# breadboard-small-with-header.net
KiCad netlist of a schematic drawn in EAGLE
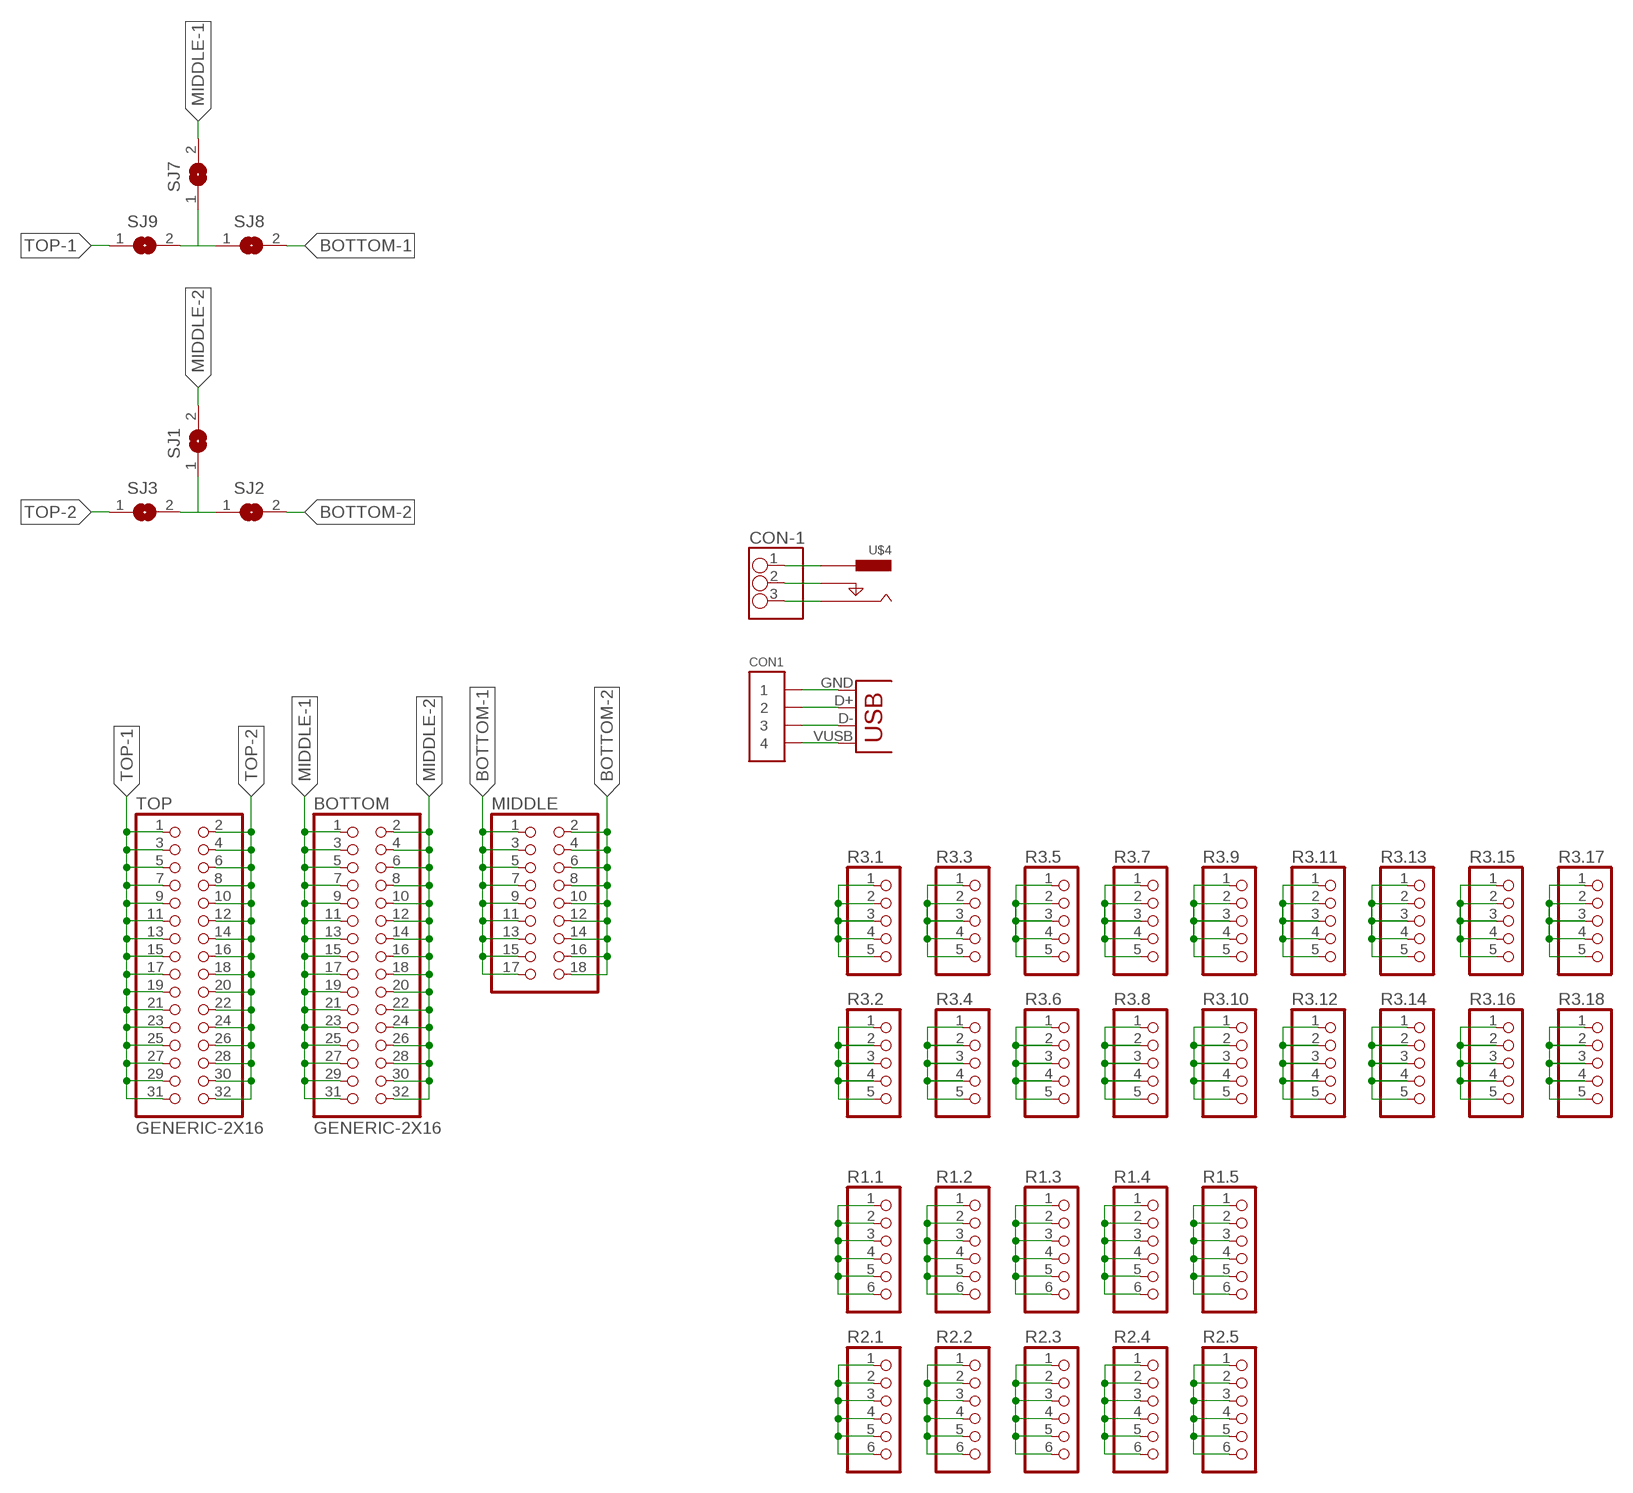
[diagram p0: schematic, sheet 1]

(export (version "E")
  (design (tool "Eeschema 10.0.6"))
  (components
    (comp (ref "BOTTOM")
      (value "GENERIC-2X16")
      (footprint "eagle-import:PINHEADER-100MIL-2X16-NOSILK")
      (libsource (lib "eagle-import") (part "GENERIC-2X16"))
    )
    (comp (ref "CON-1")
      (value "GENERIC-1X3")
      (footprint "eagle-import:PINHEADER-100MIL-1X3-NOSILK")
      (libsource (lib "eagle-import") (part "GENERIC-1X3"))
    )
    (comp (ref "CON1")
      (value "GENERIC-1X4STRAIGHT")
      (footprint "eagle-import:PINHEADER-100MIL-1X4-NOSILK")
      (libsource (lib "eagle-import") (part "GENERIC-1X4STRAIGHT"))
    )
    (comp (ref "MIDDLE")
      (value "GENERIC-2X9")
      (footprint "eagle-import:PINHEADER-100MIL-2X9-NOSILK")
      (libsource (lib "eagle-import") (part "GENERIC-2X9"))
    )
    (comp (ref "R1.1")
      (value "GENERIC-1X6")
      (footprint "eagle-import:PINHEADER-100MIL-1X6-NOSILK")
      (libsource (lib "eagle-import") (part "GENERIC-1X6"))
    )
    (comp (ref "R1.2")
      (value "GENERIC-1X6")
      (footprint "eagle-import:PINHEADER-100MIL-1X6-NOSILK")
      (libsource (lib "eagle-import") (part "GENERIC-1X6"))
    )
    (comp (ref "R1.3")
      (value "GENERIC-1X6")
      (footprint "eagle-import:PINHEADER-100MIL-1X6-NOSILK")
      (libsource (lib "eagle-import") (part "GENERIC-1X6"))
    )
    (comp (ref "R1.4")
      (value "GENERIC-1X6")
      (footprint "eagle-import:PINHEADER-100MIL-1X6-NOSILK")
      (libsource (lib "eagle-import") (part "GENERIC-1X6"))
    )
    (comp (ref "R1.5")
      (value "GENERIC-1X6")
      (footprint "eagle-import:PINHEADER-100MIL-1X6-NOSILK")
      (libsource (lib "eagle-import") (part "GENERIC-1X6"))
    )
    (comp (ref "R2.1")
      (value "GENERIC-1X6")
      (footprint "eagle-import:PINHEADER-100MIL-1X6-NOSILK")
      (libsource (lib "eagle-import") (part "GENERIC-1X6"))
    )
    (comp (ref "R2.2")
      (value "GENERIC-1X6")
      (footprint "eagle-import:PINHEADER-100MIL-1X6-NOSILK")
      (libsource (lib "eagle-import") (part "GENERIC-1X6"))
    )
    (comp (ref "R2.3")
      (value "GENERIC-1X6")
      (footprint "eagle-import:PINHEADER-100MIL-1X6-NOSILK")
      (libsource (lib "eagle-import") (part "GENERIC-1X6"))
    )
    (comp (ref "R2.4")
      (value "GENERIC-1X6")
      (footprint "eagle-import:PINHEADER-100MIL-1X6-NOSILK")
      (libsource (lib "eagle-import") (part "GENERIC-1X6"))
    )
    (comp (ref "R2.5")
      (value "GENERIC-1X6")
      (footprint "eagle-import:PINHEADER-100MIL-1X6-NOSILK")
      (libsource (lib "eagle-import") (part "GENERIC-1X6"))
    )
    (comp (ref "R3.1")
      (value "GENERIC-1X5")
      (footprint "eagle-import:PINHEADER-100MIL-1X5-NOSILK")
      (libsource (lib "eagle-import") (part "GENERIC-1X5"))
    )
    (comp (ref "R3.2")
      (value "GENERIC-1X5")
      (footprint "eagle-import:PINHEADER-100MIL-1X5-NOSILK")
      (libsource (lib "eagle-import") (part "GENERIC-1X5"))
    )
    (comp (ref "R3.3")
      (value "GENERIC-1X5")
      (footprint "eagle-import:PINHEADER-100MIL-1X5-NOSILK")
      (libsource (lib "eagle-import") (part "GENERIC-1X5"))
    )
    (comp (ref "R3.4")
      (value "GENERIC-1X5")
      (footprint "eagle-import:PINHEADER-100MIL-1X5-NOSILK")
      (libsource (lib "eagle-import") (part "GENERIC-1X5"))
    )
    (comp (ref "R3.5")
      (value "GENERIC-1X5")
      (footprint "eagle-import:PINHEADER-100MIL-1X5-NOSILK")
      (libsource (lib "eagle-import") (part "GENERIC-1X5"))
    )
    (comp (ref "R3.6")
      (value "GENERIC-1X5")
      (footprint "eagle-import:PINHEADER-100MIL-1X5-NOSILK")
      (libsource (lib "eagle-import") (part "GENERIC-1X5"))
    )
    (comp (ref "R3.7")
      (value "GENERIC-1X5")
      (footprint "eagle-import:PINHEADER-100MIL-1X5-NOSILK")
      (libsource (lib "eagle-import") (part "GENERIC-1X5"))
    )
    (comp (ref "R3.8")
      (value "GENERIC-1X5")
      (footprint "eagle-import:PINHEADER-100MIL-1X5-NOSILK")
      (libsource (lib "eagle-import") (part "GENERIC-1X5"))
    )
    (comp (ref "R3.9")
      (value "GENERIC-1X5")
      (footprint "eagle-import:PINHEADER-100MIL-1X5-NOSILK")
      (libsource (lib "eagle-import") (part "GENERIC-1X5"))
    )
    (comp (ref "R3.10")
      (value "GENERIC-1X5")
      (footprint "eagle-import:PINHEADER-100MIL-1X5-NOSILK")
      (libsource (lib "eagle-import") (part "GENERIC-1X5"))
    )
    (comp (ref "R3.11")
      (value "GENERIC-1X5")
      (footprint "eagle-import:PINHEADER-100MIL-1X5-NOSILK")
      (libsource (lib "eagle-import") (part "GENERIC-1X5"))
    )
    (comp (ref "R3.12")
      (value "GENERIC-1X5")
      (footprint "eagle-import:PINHEADER-100MIL-1X5-NOSILK")
      (libsource (lib "eagle-import") (part "GENERIC-1X5"))
    )
    (comp (ref "R3.13")
      (value "GENERIC-1X5")
      (footprint "eagle-import:PINHEADER-100MIL-1X5-NOSILK")
      (libsource (lib "eagle-import") (part "GENERIC-1X5"))
    )
    (comp (ref "R3.14")
      (value "GENERIC-1X5")
      (footprint "eagle-import:PINHEADER-100MIL-1X5-NOSILK")
      (libsource (lib "eagle-import") (part "GENERIC-1X5"))
    )
    (comp (ref "R3.15")
      (value "GENERIC-1X5")
      (footprint "eagle-import:PINHEADER-100MIL-1X5-NOSILK")
      (libsource (lib "eagle-import") (part "GENERIC-1X5"))
    )
    (comp (ref "R3.16")
      (value "GENERIC-1X5")
      (footprint "eagle-import:PINHEADER-100MIL-1X5-NOSILK")
      (libsource (lib "eagle-import") (part "GENERIC-1X5"))
    )
    (comp (ref "R3.17")
      (value "GENERIC-1X5")
      (footprint "eagle-import:PINHEADER-100MIL-1X5-NOSILK")
      (libsource (lib "eagle-import") (part "GENERIC-1X5"))
    )
    (comp (ref "R3.18")
      (value "GENERIC-1X5")
      (footprint "eagle-import:PINHEADER-100MIL-1X5-NOSILK")
      (libsource (lib "eagle-import") (part "GENERIC-1X5"))
    )
    (comp (ref "SJ1") (value "SJ") (footprint "eagle-import:SJ") (libsource (lib "eagle-import") (part "SJ")))
    (comp (ref "SJ2") (value "SJ") (footprint "eagle-import:SJ") (libsource (lib "eagle-import") (part "SJ")))
    (comp (ref "SJ3") (value "SJ") (footprint "eagle-import:SJ") (libsource (lib "eagle-import") (part "SJ")))
    (comp (ref "SJ7") (value "SJ") (footprint "eagle-import:SJ") (libsource (lib "eagle-import") (part "SJ")))
    (comp (ref "SJ8") (value "SJ") (footprint "eagle-import:SJ") (libsource (lib "eagle-import") (part "SJ")))
    (comp (ref "SJ9") (value "SJ") (footprint "eagle-import:SJ") (libsource (lib "eagle-import") (part "SJ")))
    (comp (ref "TOP")
      (value "GENERIC-2X16")
      (footprint "eagle-import:PINHEADER-100MIL-2X16-NOSILK")
      (libsource (lib "eagle-import") (part "GENERIC-2X16"))
    )
    (comp (ref "U$3")
      (value "USBMINI")
      (footprint "eagle-import:CONN_USB_MINI-B")
      (libsource (lib "eagle-import") (part "USBMINI"))
    )
    (comp (ref "U$4")
      (value "POWER-BARREL_JACKEBAY")
      (footprint "eagle-import:POWER-BARREL-2MM1-EBAY")
      (libsource (lib "eagle-import") (part "POWER-BARREL_JACKEBAY"))
    )
  )
  (nets
    (net (code "1") (name "BOTTOM-1") (class "Default")
      (node (ref "MIDDLE") (pin "1") (pinfunction "1_1") (pintype "passive"))
      (node (ref "MIDDLE") (pin "11") (pinfunction "11_11") (pintype "passive"))
      (node (ref "MIDDLE") (pin "13") (pinfunction "13_13") (pintype "passive"))
      (node (ref "MIDDLE") (pin "15") (pinfunction "15_15") (pintype "passive"))
      (node (ref "MIDDLE") (pin "17") (pinfunction "17_17") (pintype "passive"))
      (node (ref "MIDDLE") (pin "3") (pinfunction "3_3") (pintype "passive"))
      (node (ref "MIDDLE") (pin "5") (pinfunction "5_5") (pintype "passive"))
      (node (ref "MIDDLE") (pin "7") (pinfunction "7_7") (pintype "passive"))
      (node (ref "MIDDLE") (pin "9") (pinfunction "9_9") (pintype "passive"))
      (node (ref "SJ8") (pin "2") (pinfunction "2_2") (pintype "passive"))
    )
    (net (code "2") (name "BOTTOM-2") (class "Default")
      (node (ref "MIDDLE") (pin "10") (pinfunction "10_10") (pintype "passive"))
      (node (ref "MIDDLE") (pin "12") (pinfunction "12_12") (pintype "passive"))
      (node (ref "MIDDLE") (pin "14") (pinfunction "14_14") (pintype "passive"))
      (node (ref "MIDDLE") (pin "16") (pinfunction "16_16") (pintype "passive"))
      (node (ref "MIDDLE") (pin "18") (pinfunction "18_18") (pintype "passive"))
      (node (ref "MIDDLE") (pin "2") (pinfunction "2_2") (pintype "passive"))
      (node (ref "MIDDLE") (pin "4") (pinfunction "4_4") (pintype "passive"))
      (node (ref "MIDDLE") (pin "6") (pinfunction "6_6") (pintype "passive"))
      (node (ref "MIDDLE") (pin "8") (pinfunction "8_8") (pintype "passive"))
      (node (ref "SJ2") (pin "2") (pinfunction "2_2") (pintype "passive"))
    )
    (net (code "3") (name "MIDDLE-1") (class "Default")
      (node (ref "BOTTOM") (pin "1") (pinfunction "1_1") (pintype "passive"))
      (node (ref "BOTTOM") (pin "11") (pinfunction "11_11") (pintype "passive"))
      (node (ref "BOTTOM") (pin "13") (pinfunction "13_13") (pintype "passive"))
      (node (ref "BOTTOM") (pin "15") (pinfunction "15_15") (pintype "passive"))
      (node (ref "BOTTOM") (pin "17") (pinfunction "17_17") (pintype "passive"))
      (node (ref "BOTTOM") (pin "19") (pinfunction "19_19") (pintype "passive"))
      (node (ref "BOTTOM") (pin "21") (pinfunction "21_21") (pintype "passive"))
      (node (ref "BOTTOM") (pin "23") (pinfunction "23_23") (pintype "passive"))
      (node (ref "BOTTOM") (pin "25") (pinfunction "25_25") (pintype "passive"))
      (node (ref "BOTTOM") (pin "27") (pinfunction "27_27") (pintype "passive"))
      (node (ref "BOTTOM") (pin "29") (pinfunction "29_29") (pintype "passive"))
      (node (ref "BOTTOM") (pin "3") (pinfunction "3_3") (pintype "passive"))
      (node (ref "BOTTOM") (pin "31") (pinfunction "31_31") (pintype "passive"))
      (node (ref "BOTTOM") (pin "5") (pinfunction "5_5") (pintype "passive"))
      (node (ref "BOTTOM") (pin "7") (pinfunction "7_7") (pintype "passive"))
      (node (ref "BOTTOM") (pin "9") (pinfunction "9_9") (pintype "passive"))
      (node (ref "SJ7") (pin "2") (pinfunction "2_2") (pintype "passive"))
    )
    (net (code "4") (name "MIDDLE-2") (class "Default")
      (node (ref "BOTTOM") (pin "10") (pinfunction "10_10") (pintype "passive"))
      (node (ref "BOTTOM") (pin "12") (pinfunction "12_12") (pintype "passive"))
      (node (ref "BOTTOM") (pin "14") (pinfunction "14_14") (pintype "passive"))
      (node (ref "BOTTOM") (pin "16") (pinfunction "16_16") (pintype "passive"))
      (node (ref "BOTTOM") (pin "18") (pinfunction "18_18") (pintype "passive"))
      (node (ref "BOTTOM") (pin "2") (pinfunction "2_2") (pintype "passive"))
      (node (ref "BOTTOM") (pin "20") (pinfunction "20_20") (pintype "passive"))
      (node (ref "BOTTOM") (pin "22") (pinfunction "22_22") (pintype "passive"))
      (node (ref "BOTTOM") (pin "24") (pinfunction "24_24") (pintype "passive"))
      (node (ref "BOTTOM") (pin "26") (pinfunction "26_26") (pintype "passive"))
      (node (ref "BOTTOM") (pin "28") (pinfunction "28_28") (pintype "passive"))
      (node (ref "BOTTOM") (pin "30") (pinfunction "30_30") (pintype "passive"))
      (node (ref "BOTTOM") (pin "32") (pinfunction "32_32") (pintype "passive"))
      (node (ref "BOTTOM") (pin "4") (pinfunction "4_4") (pintype "passive"))
      (node (ref "BOTTOM") (pin "6") (pinfunction "6_6") (pintype "passive"))
      (node (ref "BOTTOM") (pin "8") (pinfunction "8_8") (pintype "passive"))
      (node (ref "SJ1") (pin "2") (pinfunction "2_2") (pintype "passive"))
    )
    (net (code "5") (name "Net-(CON1-Pad1)") (class "Default")
      (node (ref "CON1") (pin "1") (pinfunction "1_1") (pintype "bidirectional"))
      (node (ref "U$3") (pin "GND") (pinfunction "GND_GND") (pintype "bidirectional"))
    )
    (net (code "6") (name "Net-(CON1-Pad2)") (class "Default")
      (node (ref "CON1") (pin "2") (pinfunction "2_2") (pintype "bidirectional"))
      (node (ref "U$3") (pin "D+") (pinfunction "D+_D+") (pintype "bidirectional"))
    )
    (net (code "7") (name "Net-(CON1-Pad3)") (class "Default")
      (node (ref "CON1") (pin "3") (pinfunction "3_3") (pintype "bidirectional"))
      (node (ref "U$3") (pin "D-") (pinfunction "D-_D-") (pintype "bidirectional"))
    )
    (net (code "8") (name "Net-(R1.1-Pad1)") (class "Default")
      (node (ref "R1.1") (pin "1") (pinfunction "1_1") (pintype "passive"))
      (node (ref "R1.1") (pin "2") (pinfunction "2_2") (pintype "passive"))
      (node (ref "R1.1") (pin "3") (pinfunction "3_3") (pintype "passive"))
      (node (ref "R1.1") (pin "4") (pinfunction "4_4") (pintype "passive"))
      (node (ref "R1.1") (pin "5") (pinfunction "5_5") (pintype "passive"))
      (node (ref "R1.1") (pin "6") (pinfunction "6_6") (pintype "passive"))
    )
    (net (code "9") (name "Net-(R1.2-Pad1)") (class "Default")
      (node (ref "R1.2") (pin "1") (pinfunction "1_1") (pintype "passive"))
      (node (ref "R1.2") (pin "2") (pinfunction "2_2") (pintype "passive"))
      (node (ref "R1.2") (pin "3") (pinfunction "3_3") (pintype "passive"))
      (node (ref "R1.2") (pin "4") (pinfunction "4_4") (pintype "passive"))
      (node (ref "R1.2") (pin "5") (pinfunction "5_5") (pintype "passive"))
      (node (ref "R1.2") (pin "6") (pinfunction "6_6") (pintype "passive"))
    )
    (net (code "10") (name "Net-(R1.3-Pad1)") (class "Default")
      (node (ref "R1.3") (pin "1") (pinfunction "1_1") (pintype "passive"))
      (node (ref "R1.3") (pin "2") (pinfunction "2_2") (pintype "passive"))
      (node (ref "R1.3") (pin "3") (pinfunction "3_3") (pintype "passive"))
      (node (ref "R1.3") (pin "4") (pinfunction "4_4") (pintype "passive"))
      (node (ref "R1.3") (pin "5") (pinfunction "5_5") (pintype "passive"))
      (node (ref "R1.3") (pin "6") (pinfunction "6_6") (pintype "passive"))
    )
    (net (code "11") (name "Net-(R1.4-Pad1)") (class "Default")
      (node (ref "R1.4") (pin "1") (pinfunction "1_1") (pintype "passive"))
      (node (ref "R1.4") (pin "2") (pinfunction "2_2") (pintype "passive"))
      (node (ref "R1.4") (pin "3") (pinfunction "3_3") (pintype "passive"))
      (node (ref "R1.4") (pin "4") (pinfunction "4_4") (pintype "passive"))
      (node (ref "R1.4") (pin "5") (pinfunction "5_5") (pintype "passive"))
      (node (ref "R1.4") (pin "6") (pinfunction "6_6") (pintype "passive"))
    )
    (net (code "12") (name "Net-(R1.5-Pad1)") (class "Default")
      (node (ref "R1.5") (pin "1") (pinfunction "1_1") (pintype "passive"))
      (node (ref "R1.5") (pin "2") (pinfunction "2_2") (pintype "passive"))
      (node (ref "R1.5") (pin "3") (pinfunction "3_3") (pintype "passive"))
      (node (ref "R1.5") (pin "4") (pinfunction "4_4") (pintype "passive"))
      (node (ref "R1.5") (pin "5") (pinfunction "5_5") (pintype "passive"))
      (node (ref "R1.5") (pin "6") (pinfunction "6_6") (pintype "passive"))
    )
    (net (code "13") (name "Net-(R2.1-Pad1)") (class "Default")
      (node (ref "R2.1") (pin "1") (pinfunction "1_1") (pintype "passive"))
      (node (ref "R2.1") (pin "2") (pinfunction "2_2") (pintype "passive"))
      (node (ref "R2.1") (pin "3") (pinfunction "3_3") (pintype "passive"))
      (node (ref "R2.1") (pin "4") (pinfunction "4_4") (pintype "passive"))
      (node (ref "R2.1") (pin "5") (pinfunction "5_5") (pintype "passive"))
      (node (ref "R2.1") (pin "6") (pinfunction "6_6") (pintype "passive"))
    )
    (net (code "14") (name "Net-(R2.2-Pad1)") (class "Default")
      (node (ref "R2.2") (pin "1") (pinfunction "1_1") (pintype "passive"))
      (node (ref "R2.2") (pin "2") (pinfunction "2_2") (pintype "passive"))
      (node (ref "R2.2") (pin "3") (pinfunction "3_3") (pintype "passive"))
      (node (ref "R2.2") (pin "4") (pinfunction "4_4") (pintype "passive"))
      (node (ref "R2.2") (pin "5") (pinfunction "5_5") (pintype "passive"))
      (node (ref "R2.2") (pin "6") (pinfunction "6_6") (pintype "passive"))
    )
    (net (code "15") (name "Net-(R2.3-Pad1)") (class "Default")
      (node (ref "R2.3") (pin "1") (pinfunction "1_1") (pintype "passive"))
      (node (ref "R2.3") (pin "2") (pinfunction "2_2") (pintype "passive"))
      (node (ref "R2.3") (pin "3") (pinfunction "3_3") (pintype "passive"))
      (node (ref "R2.3") (pin "4") (pinfunction "4_4") (pintype "passive"))
      (node (ref "R2.3") (pin "5") (pinfunction "5_5") (pintype "passive"))
      (node (ref "R2.3") (pin "6") (pinfunction "6_6") (pintype "passive"))
    )
    (net (code "16") (name "Net-(R2.4-Pad1)") (class "Default")
      (node (ref "R2.4") (pin "1") (pinfunction "1_1") (pintype "passive"))
      (node (ref "R2.4") (pin "2") (pinfunction "2_2") (pintype "passive"))
      (node (ref "R2.4") (pin "3") (pinfunction "3_3") (pintype "passive"))
      (node (ref "R2.4") (pin "4") (pinfunction "4_4") (pintype "passive"))
      (node (ref "R2.4") (pin "5") (pinfunction "5_5") (pintype "passive"))
      (node (ref "R2.4") (pin "6") (pinfunction "6_6") (pintype "passive"))
    )
    (net (code "17") (name "Net-(R2.5-Pad1)") (class "Default")
      (node (ref "R2.5") (pin "1") (pinfunction "1_1") (pintype "passive"))
      (node (ref "R2.5") (pin "2") (pinfunction "2_2") (pintype "passive"))
      (node (ref "R2.5") (pin "3") (pinfunction "3_3") (pintype "passive"))
      (node (ref "R2.5") (pin "4") (pinfunction "4_4") (pintype "passive"))
      (node (ref "R2.5") (pin "5") (pinfunction "5_5") (pintype "passive"))
      (node (ref "R2.5") (pin "6") (pinfunction "6_6") (pintype "passive"))
    )
    (net (code "18") (name "Net-(R3.1-Pad1)") (class "Default")
      (node (ref "R3.1") (pin "1") (pinfunction "1_1") (pintype "passive"))
      (node (ref "R3.1") (pin "2") (pinfunction "2_2") (pintype "passive"))
      (node (ref "R3.1") (pin "3") (pinfunction "3_3") (pintype "passive"))
      (node (ref "R3.1") (pin "4") (pinfunction "4_4") (pintype "passive"))
      (node (ref "R3.1") (pin "5") (pinfunction "5_5") (pintype "passive"))
    )
    (net (code "19") (name "Net-(R3.2-Pad1)") (class "Default")
      (node (ref "R3.2") (pin "1") (pinfunction "1_1") (pintype "passive"))
      (node (ref "R3.2") (pin "2") (pinfunction "2_2") (pintype "passive"))
      (node (ref "R3.2") (pin "3") (pinfunction "3_3") (pintype "passive"))
      (node (ref "R3.2") (pin "4") (pinfunction "4_4") (pintype "passive"))
      (node (ref "R3.2") (pin "5") (pinfunction "5_5") (pintype "passive"))
    )
    (net (code "20") (name "Net-(R3.3-Pad1)") (class "Default")
      (node (ref "R3.3") (pin "1") (pinfunction "1_1") (pintype "passive"))
      (node (ref "R3.3") (pin "2") (pinfunction "2_2") (pintype "passive"))
      (node (ref "R3.3") (pin "3") (pinfunction "3_3") (pintype "passive"))
      (node (ref "R3.3") (pin "4") (pinfunction "4_4") (pintype "passive"))
      (node (ref "R3.3") (pin "5") (pinfunction "5_5") (pintype "passive"))
    )
    (net (code "21") (name "Net-(R3.4-Pad1)") (class "Default")
      (node (ref "R3.4") (pin "1") (pinfunction "1_1") (pintype "passive"))
      (node (ref "R3.4") (pin "2") (pinfunction "2_2") (pintype "passive"))
      (node (ref "R3.4") (pin "3") (pinfunction "3_3") (pintype "passive"))
      (node (ref "R3.4") (pin "4") (pinfunction "4_4") (pintype "passive"))
      (node (ref "R3.4") (pin "5") (pinfunction "5_5") (pintype "passive"))
    )
    (net (code "22") (name "Net-(R3.5-Pad1)") (class "Default")
      (node (ref "R3.5") (pin "1") (pinfunction "1_1") (pintype "passive"))
      (node (ref "R3.5") (pin "2") (pinfunction "2_2") (pintype "passive"))
      (node (ref "R3.5") (pin "3") (pinfunction "3_3") (pintype "passive"))
      (node (ref "R3.5") (pin "4") (pinfunction "4_4") (pintype "passive"))
      (node (ref "R3.5") (pin "5") (pinfunction "5_5") (pintype "passive"))
    )
    (net (code "23") (name "Net-(R3.6-Pad1)") (class "Default")
      (node (ref "R3.6") (pin "1") (pinfunction "1_1") (pintype "passive"))
      (node (ref "R3.6") (pin "2") (pinfunction "2_2") (pintype "passive"))
      (node (ref "R3.6") (pin "3") (pinfunction "3_3") (pintype "passive"))
      (node (ref "R3.6") (pin "4") (pinfunction "4_4") (pintype "passive"))
      (node (ref "R3.6") (pin "5") (pinfunction "5_5") (pintype "passive"))
    )
    (net (code "24") (name "Net-(R3.7-Pad1)") (class "Default")
      (node (ref "R3.7") (pin "1") (pinfunction "1_1") (pintype "passive"))
      (node (ref "R3.7") (pin "2") (pinfunction "2_2") (pintype "passive"))
      (node (ref "R3.7") (pin "3") (pinfunction "3_3") (pintype "passive"))
      (node (ref "R3.7") (pin "4") (pinfunction "4_4") (pintype "passive"))
      (node (ref "R3.7") (pin "5") (pinfunction "5_5") (pintype "passive"))
    )
    (net (code "25") (name "Net-(R3.8-Pad1)") (class "Default")
      (node (ref "R3.8") (pin "1") (pinfunction "1_1") (pintype "passive"))
      (node (ref "R3.8") (pin "2") (pinfunction "2_2") (pintype "passive"))
      (node (ref "R3.8") (pin "3") (pinfunction "3_3") (pintype "passive"))
      (node (ref "R3.8") (pin "4") (pinfunction "4_4") (pintype "passive"))
      (node (ref "R3.8") (pin "5") (pinfunction "5_5") (pintype "passive"))
    )
    (net (code "26") (name "Net-(R3.9-Pad1)") (class "Default")
      (node (ref "R3.9") (pin "1") (pinfunction "1_1") (pintype "passive"))
      (node (ref "R3.9") (pin "2") (pinfunction "2_2") (pintype "passive"))
      (node (ref "R3.9") (pin "3") (pinfunction "3_3") (pintype "passive"))
      (node (ref "R3.9") (pin "4") (pinfunction "4_4") (pintype "passive"))
      (node (ref "R3.9") (pin "5") (pinfunction "5_5") (pintype "passive"))
    )
    (net (code "27") (name "Net-(R3.10-Pad1)") (class "Default")
      (node (ref "R3.10") (pin "1") (pinfunction "1_1") (pintype "passive"))
      (node (ref "R3.10") (pin "2") (pinfunction "2_2") (pintype "passive"))
      (node (ref "R3.10") (pin "3") (pinfunction "3_3") (pintype "passive"))
      (node (ref "R3.10") (pin "4") (pinfunction "4_4") (pintype "passive"))
      (node (ref "R3.10") (pin "5") (pinfunction "5_5") (pintype "passive"))
    )
    (net (code "28") (name "Net-(R3.11-Pad1)") (class "Default")
      (node (ref "R3.11") (pin "1") (pinfunction "1_1") (pintype "passive"))
      (node (ref "R3.11") (pin "2") (pinfunction "2_2") (pintype "passive"))
      (node (ref "R3.11") (pin "3") (pinfunction "3_3") (pintype "passive"))
      (node (ref "R3.11") (pin "4") (pinfunction "4_4") (pintype "passive"))
      (node (ref "R3.11") (pin "5") (pinfunction "5_5") (pintype "passive"))
    )
    (net (code "29") (name "Net-(R3.12-Pad1)") (class "Default")
      (node (ref "R3.12") (pin "1") (pinfunction "1_1") (pintype "passive"))
      (node (ref "R3.12") (pin "2") (pinfunction "2_2") (pintype "passive"))
      (node (ref "R3.12") (pin "3") (pinfunction "3_3") (pintype "passive"))
      (node (ref "R3.12") (pin "4") (pinfunction "4_4") (pintype "passive"))
      (node (ref "R3.12") (pin "5") (pinfunction "5_5") (pintype "passive"))
    )
    (net (code "30") (name "Net-(R3.13-Pad1)") (class "Default")
      (node (ref "R3.13") (pin "1") (pinfunction "1_1") (pintype "passive"))
      (node (ref "R3.13") (pin "2") (pinfunction "2_2") (pintype "passive"))
      (node (ref "R3.13") (pin "3") (pinfunction "3_3") (pintype "passive"))
      (node (ref "R3.13") (pin "4") (pinfunction "4_4") (pintype "passive"))
      (node (ref "R3.13") (pin "5") (pinfunction "5_5") (pintype "passive"))
    )
    (net (code "31") (name "Net-(R3.14-Pad1)") (class "Default")
      (node (ref "R3.14") (pin "1") (pinfunction "1_1") (pintype "passive"))
      (node (ref "R3.14") (pin "2") (pinfunction "2_2") (pintype "passive"))
      (node (ref "R3.14") (pin "3") (pinfunction "3_3") (pintype "passive"))
      (node (ref "R3.14") (pin "4") (pinfunction "4_4") (pintype "passive"))
      (node (ref "R3.14") (pin "5") (pinfunction "5_5") (pintype "passive"))
    )
    (net (code "32") (name "Net-(R3.15-Pad1)") (class "Default")
      (node (ref "R3.15") (pin "1") (pinfunction "1_1") (pintype "passive"))
      (node (ref "R3.15") (pin "2") (pinfunction "2_2") (pintype "passive"))
      (node (ref "R3.15") (pin "3") (pinfunction "3_3") (pintype "passive"))
      (node (ref "R3.15") (pin "4") (pinfunction "4_4") (pintype "passive"))
      (node (ref "R3.15") (pin "5") (pinfunction "5_5") (pintype "passive"))
    )
    (net (code "33") (name "Net-(R3.16-Pad1)") (class "Default")
      (node (ref "R3.16") (pin "1") (pinfunction "1_1") (pintype "passive"))
      (node (ref "R3.16") (pin "2") (pinfunction "2_2") (pintype "passive"))
      (node (ref "R3.16") (pin "3") (pinfunction "3_3") (pintype "passive"))
      (node (ref "R3.16") (pin "4") (pinfunction "4_4") (pintype "passive"))
      (node (ref "R3.16") (pin "5") (pinfunction "5_5") (pintype "passive"))
    )
    (net (code "34") (name "Net-(R3.17-Pad1)") (class "Default")
      (node (ref "R3.17") (pin "1") (pinfunction "1_1") (pintype "passive"))
      (node (ref "R3.17") (pin "2") (pinfunction "2_2") (pintype "passive"))
      (node (ref "R3.17") (pin "3") (pinfunction "3_3") (pintype "passive"))
      (node (ref "R3.17") (pin "4") (pinfunction "4_4") (pintype "passive"))
      (node (ref "R3.17") (pin "5") (pinfunction "5_5") (pintype "passive"))
    )
    (net (code "35") (name "Net-(R3.18-Pad1)") (class "Default")
      (node (ref "R3.18") (pin "1") (pinfunction "1_1") (pintype "passive"))
      (node (ref "R3.18") (pin "2") (pinfunction "2_2") (pintype "passive"))
      (node (ref "R3.18") (pin "3") (pinfunction "3_3") (pintype "passive"))
      (node (ref "R3.18") (pin "4") (pinfunction "4_4") (pintype "passive"))
      (node (ref "R3.18") (pin "5") (pinfunction "5_5") (pintype "passive"))
    )
    (net (code "36") (name "Net-(SJ1-Pad1)") (class "Default")
      (node (ref "SJ1") (pin "1") (pinfunction "1_1") (pintype "passive"))
      (node (ref "SJ2") (pin "1") (pinfunction "1_1") (pintype "passive"))
      (node (ref "SJ3") (pin "2") (pinfunction "2_2") (pintype "passive"))
    )
    (net (code "37") (name "Net-(SJ7-Pad1)") (class "Default")
      (node (ref "SJ7") (pin "1") (pinfunction "1_1") (pintype "passive"))
      (node (ref "SJ8") (pin "1") (pinfunction "1_1") (pintype "passive"))
      (node (ref "SJ9") (pin "2") (pinfunction "2_2") (pintype "passive"))
    )
    (net (code "38") (name "Net-(U$3-VBUS)") (class "Default")
      (node (ref "CON1") (pin "4") (pinfunction "4_4") (pintype "bidirectional"))
      (node (ref "U$3") (pin "VUSB") (pinfunction "VBUS_VUSB") (pintype "bidirectional"))
    )
    (net (code "39") (name "Net-(U$4-CENTER)") (class "Default")
      (node (ref "CON-1") (pin "1") (pinfunction "1_1") (pintype "bidirectional"))
      (node (ref "U$4") (pin "P$4") (pinfunction "CENTER_P$4") (pintype "bidirectional"))
    )
    (net (code "40") (name "Net-(U$4-OUTER)") (class "Default")
      (node (ref "CON-1") (pin "3") (pinfunction "3_3") (pintype "bidirectional"))
      (node (ref "U$4") (pin "P$3") (pinfunction "OUTER_P$3") (pintype "bidirectional"))
    )
    (net (code "41") (name "Net-(U$4-SWITCH)") (class "Default")
      (node (ref "CON-1") (pin "2") (pinfunction "2_2") (pintype "bidirectional"))
      (node (ref "U$4") (pin "P$2") (pinfunction "SWITCH_P$2") (pintype "bidirectional"))
    )
    (net (code "42") (name "TOP-1") (class "Default")
      (node (ref "SJ9") (pin "1") (pinfunction "1_1") (pintype "passive"))
      (node (ref "TOP") (pin "1") (pinfunction "1_1") (pintype "passive"))
      (node (ref "TOP") (pin "11") (pinfunction "11_11") (pintype "passive"))
      (node (ref "TOP") (pin "13") (pinfunction "13_13") (pintype "passive"))
      (node (ref "TOP") (pin "15") (pinfunction "15_15") (pintype "passive"))
      (node (ref "TOP") (pin "17") (pinfunction "17_17") (pintype "passive"))
      (node (ref "TOP") (pin "19") (pinfunction "19_19") (pintype "passive"))
      (node (ref "TOP") (pin "21") (pinfunction "21_21") (pintype "passive"))
      (node (ref "TOP") (pin "23") (pinfunction "23_23") (pintype "passive"))
      (node (ref "TOP") (pin "25") (pinfunction "25_25") (pintype "passive"))
      (node (ref "TOP") (pin "27") (pinfunction "27_27") (pintype "passive"))
      (node (ref "TOP") (pin "29") (pinfunction "29_29") (pintype "passive"))
      (node (ref "TOP") (pin "3") (pinfunction "3_3") (pintype "passive"))
      (node (ref "TOP") (pin "31") (pinfunction "31_31") (pintype "passive"))
      (node (ref "TOP") (pin "5") (pinfunction "5_5") (pintype "passive"))
      (node (ref "TOP") (pin "7") (pinfunction "7_7") (pintype "passive"))
      (node (ref "TOP") (pin "9") (pinfunction "9_9") (pintype "passive"))
    )
    (net (code "43") (name "TOP-2") (class "Default")
      (node (ref "SJ3") (pin "1") (pinfunction "1_1") (pintype "passive"))
      (node (ref "TOP") (pin "10") (pinfunction "10_10") (pintype "passive"))
      (node (ref "TOP") (pin "12") (pinfunction "12_12") (pintype "passive"))
      (node (ref "TOP") (pin "14") (pinfunction "14_14") (pintype "passive"))
      (node (ref "TOP") (pin "16") (pinfunction "16_16") (pintype "passive"))
      (node (ref "TOP") (pin "18") (pinfunction "18_18") (pintype "passive"))
      (node (ref "TOP") (pin "2") (pinfunction "2_2") (pintype "passive"))
      (node (ref "TOP") (pin "20") (pinfunction "20_20") (pintype "passive"))
      (node (ref "TOP") (pin "22") (pinfunction "22_22") (pintype "passive"))
      (node (ref "TOP") (pin "24") (pinfunction "24_24") (pintype "passive"))
      (node (ref "TOP") (pin "26") (pinfunction "26_26") (pintype "passive"))
      (node (ref "TOP") (pin "28") (pinfunction "28_28") (pintype "passive"))
      (node (ref "TOP") (pin "30") (pinfunction "30_30") (pintype "passive"))
      (node (ref "TOP") (pin "32") (pinfunction "32_32") (pintype "passive"))
      (node (ref "TOP") (pin "4") (pinfunction "4_4") (pintype "passive"))
      (node (ref "TOP") (pin "6") (pinfunction "6_6") (pintype "passive"))
      (node (ref "TOP") (pin "8") (pinfunction "8_8") (pintype "passive"))
    )
  )
)
